# 24_064.net
KiCad netlist of a schematic drawn in Altium Designer
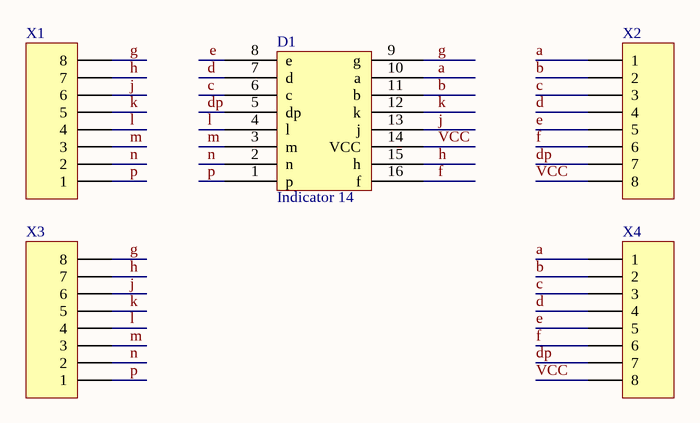
[diagram p0: 24.064.SchDoc]

(export (version "E")
  (design (tool "Eeschema 10.0.6"))
  (components
    (comp (ref "D1")
      (value "Indicator 14")
      (footprint "INDICATIR 14")
      (libsource (lib "msp_SchLib") (part "Indicator 14"))
    )
    (comp (ref "X1")
      (value "Header 8")
      (footprint "HDR1X8")
      (description "Header, 8-Pin")
      (fields (field (name "PUBLISHER") "Altium Limited"))
      (libsource (lib "Miscellaneous Connectors") (part "Header 8"))
    )
    (comp (ref "X2")
      (value "Header 8")
      (footprint "HDR1X8")
      (description "Header, 8-Pin")
      (fields (field (name "PUBLISHER") "Altium Limited"))
      (libsource (lib "") (part "Header 8_1"))
    )
    (comp (ref "X3")
      (value "Header 8")
      (footprint "HDR1X8")
      (description "Header, 8-Pin")
      (fields (field (name "PUBLISHER") "Altium Limited"))
      (libsource (lib "Miscellaneous Connectors") (part "Header 8"))
    )
    (comp (ref "X4")
      (value "Header 8")
      (footprint "HDR1X8")
      (description "Header, 8-Pin")
      (fields (field (name "PUBLISHER") "Altium Limited"))
      (libsource (lib "") (part "Header 8_1"))
    )
  )
  (nets
    (net (code "1") (name "/VCC") (class "Default")
      (node (ref "D1") (pin "14") (pinfunction "VCC_14") (pintype "passive"))
      (node (ref "X2") (pin "8") (pinfunction "8_8") (pintype "passive"))
      (node (ref "X4") (pin "8") (pinfunction "8_8") (pintype "passive"))
    )
    (net (code "2") (name "/a") (class "Default")
      (node (ref "D1") (pin "10") (pinfunction "a_10") (pintype "passive"))
      (node (ref "X2") (pin "1") (pinfunction "1_1") (pintype "passive"))
      (node (ref "X4") (pin "1") (pinfunction "1_1") (pintype "passive"))
    )
    (net (code "3") (name "/b") (class "Default")
      (node (ref "D1") (pin "11") (pinfunction "b_11") (pintype "passive"))
      (node (ref "X2") (pin "2") (pinfunction "2_2") (pintype "passive"))
      (node (ref "X4") (pin "2") (pinfunction "2_2") (pintype "passive"))
    )
    (net (code "4") (name "/c") (class "Default")
      (node (ref "D1") (pin "6") (pinfunction "c_6") (pintype "passive"))
      (node (ref "X2") (pin "3") (pinfunction "3_3") (pintype "passive"))
      (node (ref "X4") (pin "3") (pinfunction "3_3") (pintype "passive"))
    )
    (net (code "5") (name "/d") (class "Default")
      (node (ref "D1") (pin "7") (pinfunction "d_7") (pintype "passive"))
      (node (ref "X2") (pin "4") (pinfunction "4_4") (pintype "passive"))
      (node (ref "X4") (pin "4") (pinfunction "4_4") (pintype "passive"))
    )
    (net (code "6") (name "/dp") (class "Default")
      (node (ref "D1") (pin "5") (pinfunction "dp_5") (pintype "passive"))
      (node (ref "X2") (pin "7") (pinfunction "7_7") (pintype "passive"))
      (node (ref "X4") (pin "7") (pinfunction "7_7") (pintype "passive"))
    )
    (net (code "7") (name "/e") (class "Default")
      (node (ref "D1") (pin "8") (pinfunction "e_8") (pintype "passive"))
      (node (ref "X2") (pin "5") (pinfunction "5_5") (pintype "passive"))
      (node (ref "X4") (pin "5") (pinfunction "5_5") (pintype "passive"))
    )
    (net (code "8") (name "/f") (class "Default")
      (node (ref "D1") (pin "16") (pinfunction "f_16") (pintype "passive"))
      (node (ref "X2") (pin "6") (pinfunction "6_6") (pintype "passive"))
      (node (ref "X4") (pin "6") (pinfunction "6_6") (pintype "passive"))
    )
    (net (code "9") (name "/g") (class "Default")
      (node (ref "D1") (pin "9") (pinfunction "g_9") (pintype "passive"))
      (node (ref "X1") (pin "8") (pinfunction "8_8") (pintype "passive"))
      (node (ref "X3") (pin "8") (pinfunction "8_8") (pintype "passive"))
    )
    (net (code "10") (name "/h") (class "Default")
      (node (ref "D1") (pin "15") (pinfunction "h_15") (pintype "passive"))
      (node (ref "X1") (pin "7") (pinfunction "7_7") (pintype "passive"))
      (node (ref "X3") (pin "7") (pinfunction "7_7") (pintype "passive"))
    )
    (net (code "11") (name "/j") (class "Default")
      (node (ref "D1") (pin "13") (pinfunction "j_13") (pintype "passive"))
      (node (ref "X1") (pin "6") (pinfunction "6_6") (pintype "passive"))
      (node (ref "X3") (pin "6") (pinfunction "6_6") (pintype "passive"))
    )
    (net (code "12") (name "/k") (class "Default")
      (node (ref "D1") (pin "12") (pinfunction "k_12") (pintype "passive"))
      (node (ref "X1") (pin "5") (pinfunction "5_5") (pintype "passive"))
      (node (ref "X3") (pin "5") (pinfunction "5_5") (pintype "passive"))
    )
    (net (code "13") (name "/l") (class "Default")
      (node (ref "D1") (pin "4") (pinfunction "l_4") (pintype "passive"))
      (node (ref "X1") (pin "4") (pinfunction "4_4") (pintype "passive"))
      (node (ref "X3") (pin "4") (pinfunction "4_4") (pintype "passive"))
    )
    (net (code "14") (name "/m") (class "Default")
      (node (ref "D1") (pin "3") (pinfunction "m_3") (pintype "passive"))
      (node (ref "X1") (pin "3") (pinfunction "3_3") (pintype "passive"))
      (node (ref "X3") (pin "3") (pinfunction "3_3") (pintype "passive"))
    )
    (net (code "15") (name "/n") (class "Default")
      (node (ref "D1") (pin "2") (pinfunction "n_2") (pintype "passive"))
      (node (ref "X1") (pin "2") (pinfunction "2_2") (pintype "passive"))
      (node (ref "X3") (pin "2") (pinfunction "2_2") (pintype "passive"))
    )
    (net (code "16") (name "/p") (class "Default")
      (node (ref "D1") (pin "1") (pinfunction "p_1") (pintype "passive"))
      (node (ref "X1") (pin "1") (pinfunction "1_1") (pintype "passive"))
      (node (ref "X3") (pin "1") (pinfunction "1_1") (pintype "passive"))
    )
  )
)
